# SCH_long_last_clock_v3_2022-12-24.net
KiCad netlist of a schematic drawn in EasyEDA
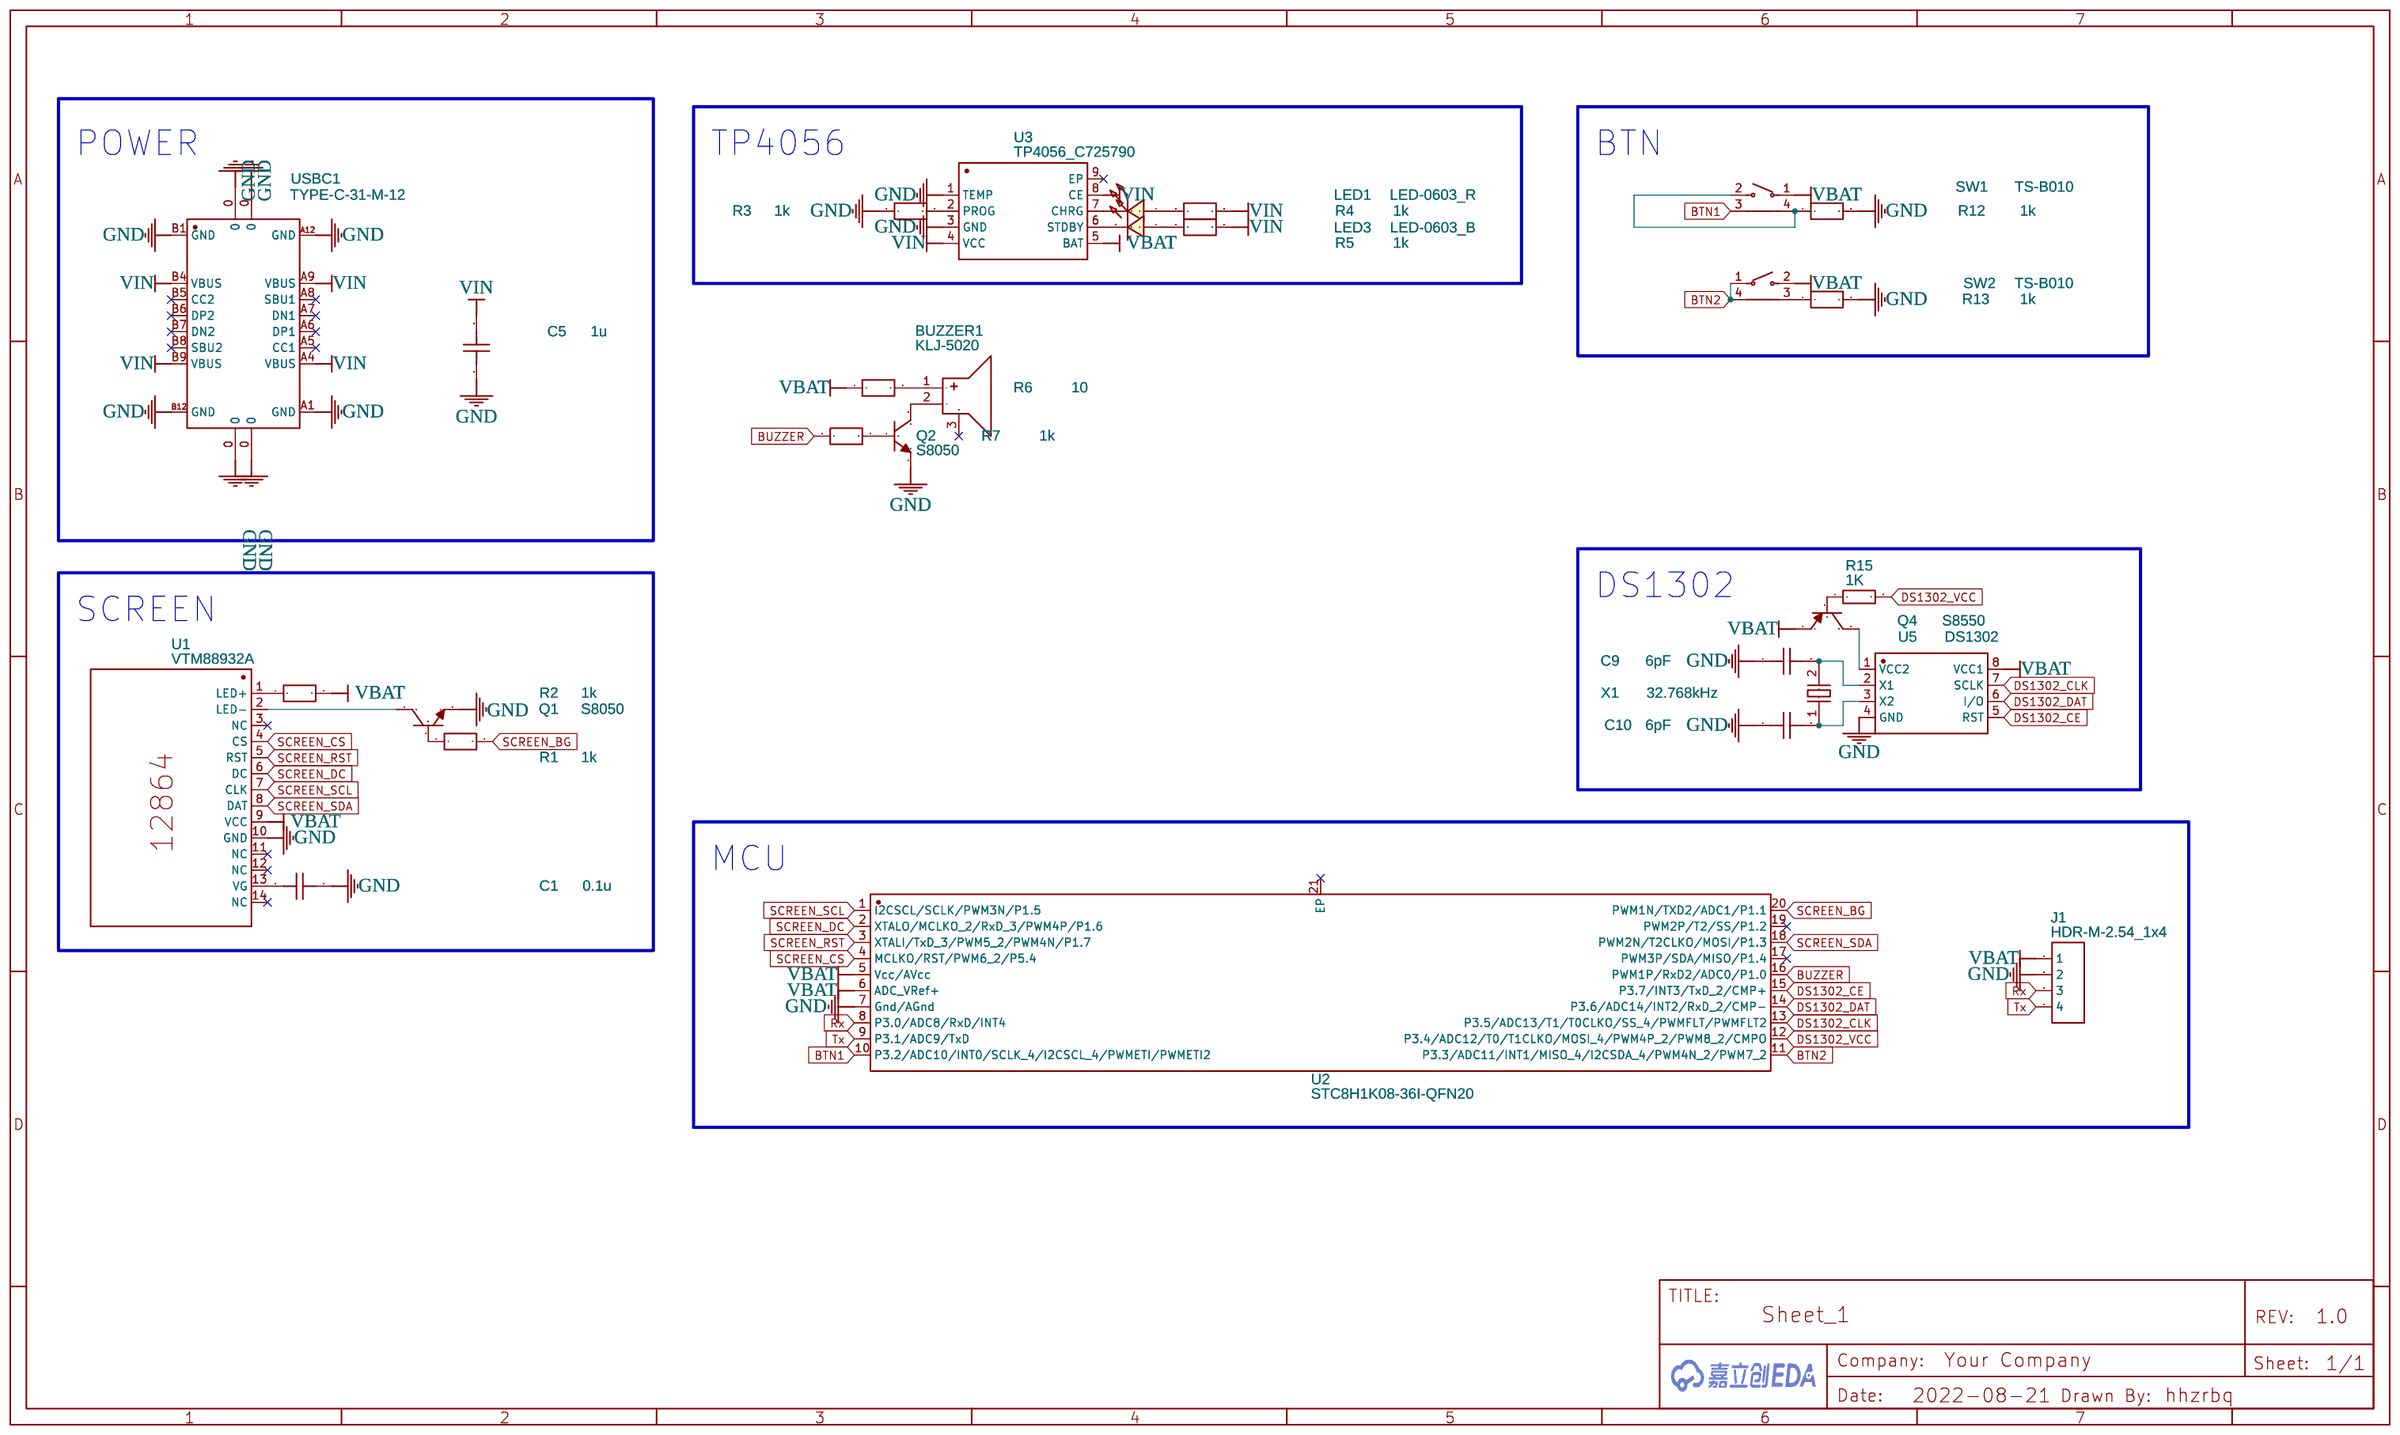
[diagram p0: schematic sheet]

(export (version "E")
  (design (tool "Eeschema 10.0.6"))
  (components
    (comp (ref "BUZZER1")
      (value "KLJ-5020")
      (fields (field (name "BOM_Supplier Part") "C556937"))
      (libsource (lib "") (part "KLJ-5020"))
    )
    (comp (ref "C1") (value "0.1u") (libsource (lib "") (part "C_0603_US")))
    (comp (ref "C5") (value "1u") (libsource (lib "") (part "C_0603_US_1")))
    (comp (ref "C9") (value "6pF") (libsource (lib "") (part "C_0603_US")))
    (comp (ref "C10") (value "6pF") (libsource (lib "") (part "C_0603_US")))
    (comp (ref "J1")
      (value "HDR-M-2.54_1x4")
      (fields (field (name "BOM_Supplier Part") "C124378"))
      (libsource (lib "") (part "HDR-M-2.54_1x4"))
    )
    (comp (ref "LED1")
      (value "LED-0603_R")
      (fields
        (field (name "BOM_Manufacturer Part") "19-217/R6C-AL1M2VY/3T")
        (field (name "BOM_Supplier Part") "C72044")
      )
      (libsource (lib "") (part "LED-0603_R"))
    )
    (comp (ref "LED3")
      (value "LED-0603_B")
      (fields
        (field (name "BOM_Manufacturer Part") "19-217/BHC-ZL1M2RY/3T")
        (field (name "BOM_Supplier Part") "C72041")
      )
      (libsource (lib "") (part "LED-0603_B"))
    )
    (comp (ref "Q1")
      (value "S8050")
      (fields (field (name "BOM_Supplier Part") "C908252"))
      (libsource (lib "") (part "S8050_C908252"))
    )
    (comp (ref "Q2")
      (value "S8050")
      (fields (field (name "BOM_Supplier Part") "C908252"))
      (libsource (lib "") (part "S8050_C908252_1"))
    )
    (comp (ref "Q4")
      (value "S8550")
      (fields (field (name "BOM_Supplier Part") "C2894712"))
      (libsource (lib "") (part "S8550_C2894712"))
    )
    (comp (ref "R1") (value "1k") (libsource (lib "") (part "R_0603_EU")))
    (comp (ref "R2") (value "1k") (libsource (lib "") (part "R_0603_EU")))
    (comp (ref "R3") (value "1k") (libsource (lib "") (part "R_0603_EU")))
    (comp (ref "R4") (value "1k") (libsource (lib "") (part "R_0603_EU")))
    (comp (ref "R5") (value "1k") (libsource (lib "") (part "R_0603_EU")))
    (comp (ref "R6") (value "10") (libsource (lib "") (part "R_0603_EU")))
    (comp (ref "R7") (value "1k") (libsource (lib "") (part "R_0603_EU")))
    (comp (ref "R12") (value "1k") (libsource (lib "") (part "R_0603_EU")))
    (comp (ref "R13") (value "1k") (libsource (lib "") (part "R_0603_EU")))
    (comp (ref "R15")
      (value "1K")
      (fields
        (field (name "BOM_Manufacturer Part") "RK73B2ATTD102J")
        (field (name "BOM_Supplier Part") "C159911")
      )
      (libsource (lib "") (part "RK73B2ATTD102J"))
    )
    (comp (ref "SW1") (value "TS-B010") (libsource (lib "") (part "TD-1100SA-250")))
    (comp (ref "SW2") (value "TS-B010") (libsource (lib "") (part "TD-1100SA-250_1")))
    (comp (ref "U1") (value "VTM88932A") (libsource (lib "") (part "VTM88932A")))
    (comp (ref "U2")
      (value "STC8H1K08-36I-QFN20")
      (fields (field (name "BOM_Supplier Part") "C915674"))
      (libsource (lib "") (part "STC8H1K08-36I-QFN20"))
    )
    (comp (ref "U3")
      (value "TP4056_C725790")
      (fields (field (name "BOM_Manufacturer Part") "TP4056") (field (name "BOM_Supplier Part") "C725790"))
      (libsource (lib "") (part "TP4056_C725790"))
    )
    (comp (ref "U5")
      (value "DS1302")
      (fields
        (field (name "BOM_Manufacturer Part") "DS1302M/TR")
        (field (name "BOM_Supplier Part") "C910881")
      )
      (libsource (lib "") (part "DS1302M/TR_C910881"))
    )
    (comp (ref "USBC1")
      (value "TYPE-C-31-M-12")
      (fields (field (name "BOM_Supplier Part") "C165948"))
      (libsource (lib "") (part "TYPE-C-31-M-12"))
    )
    (comp (ref "X1")
      (value "32.768kHz")
      (fields
        (field (name "BOM_Manufacturer Part") "Q13FC13500005")
        (field (name "BOM_Supplier Part") "C841881")
      )
      (libsource (lib "") (part "Q13FC13500005"))
    )
  )
  (nets
    (net (code "1") (name "BTN1") (class "Default")
      (node (ref "SW1") (pin "3") (pinfunction "3_3") (pintype "unspecified"))
      (node (ref "U2") (pin "10") (pinfunction "P3.2/ADC10/INT0/SCLK_4/I2CSCL_4/PWMETI/PWMETI2_10") (pintype "unspecified"))
    )
    (net (code "2") (name "BTN2") (class "Default")
      (node (ref "SW2") (pin "1") (pinfunction "1_1") (pintype "unspecified"))
      (node (ref "SW2") (pin "4") (pinfunction "4_4") (pintype "unspecified"))
      (node (ref "U2") (pin "11") (pinfunction "P3.3/ADC11/INT1/MISO_4/I2CSDA_4/PWM4N_2/PWM7_2_11") (pintype "unspecified"))
    )
    (net (code "3") (name "BUZZER") (class "Default")
      (node (ref "R7") (pin "1") (pinfunction "1_1") (pintype "unspecified"))
      (node (ref "U2") (pin "16") (pinfunction "PWM1P/RxD2/ADC0/P1.0_16") (pintype "unspecified"))
    )
    (net (code "4") (name "DS1302_CE") (class "Default")
      (node (ref "U2") (pin "15") (pinfunction "P3.7/INT3/TxD_2/CMP+_15") (pintype "unspecified"))
      (node (ref "U5") (pin "5") (pinfunction "RST_5") (pintype "unspecified"))
    )
    (net (code "5") (name "DS1302_CLK") (class "Default")
      (node (ref "U2") (pin "13") (pinfunction "P3.5/ADC13/T1/T0CLKO/SS_4/PWMFLT/PWMFLT2_13") (pintype "unspecified"))
      (node (ref "U5") (pin "7") (pinfunction "SCLK_7") (pintype "unspecified"))
    )
    (net (code "6") (name "DS1302_DAT") (class "Default")
      (node (ref "U2") (pin "14") (pinfunction "P3.6/ADC14/INT2/RxD_2/CMP-_14") (pintype "unspecified"))
      (node (ref "U5") (pin "6") (pinfunction "I/O_6") (pintype "unspecified"))
    )
    (net (code "7") (name "DS1302_VCC") (class "Default")
      (node (ref "R15") (pin "2") (pinfunction "2_2") (pintype "unspecified"))
      (node (ref "U2") (pin "12") (pinfunction "P3.4/ADC12/T0/T1CLKO/MOSI_4/PWM4P_2/PWM8_2/CMPO_12") (pintype "unspecified"))
    )
    (net (code "8") (name "GND") (class "Default")
      (node (ref "C1") (pin "2") (pinfunction "2_2") (pintype "unspecified"))
      (node (ref "C10") (pin "1") (pinfunction "1_1") (pintype "unspecified"))
      (node (ref "C5") (pin "1") (pinfunction "1_1") (pintype "unspecified"))
      (node (ref "C9") (pin "1") (pinfunction "1_1") (pintype "unspecified"))
      (node (ref "J1") (pin "2") (pinfunction "2_2") (pintype "unspecified"))
      (node (ref "Q1") (pin "2") (pinfunction "E_2") (pintype "input"))
      (node (ref "Q2") (pin "2") (pinfunction "E_2") (pintype "input"))
      (node (ref "R12") (pin "2") (pinfunction "2_2") (pintype "unspecified"))
      (node (ref "R13") (pin "2") (pinfunction "2_2") (pintype "unspecified"))
      (node (ref "R3") (pin "1") (pinfunction "1_1") (pintype "unspecified"))
      (node (ref "U1") (pin "10") (pinfunction "GND_10") (pintype "unspecified"))
      (node (ref "U2") (pin "7") (pinfunction "Gnd/AGnd_7") (pintype "unspecified"))
      (node (ref "U3") (pin "1") (pinfunction "TEMP_1") (pintype "unspecified"))
      (node (ref "U3") (pin "3") (pinfunction "GND_3") (pintype "unspecified"))
      (node (ref "U5") (pin "4") (pinfunction "GND_4") (pintype "unspecified"))
      (node (ref "USBC1") (pin "0") (pinfunction "0_0") (pintype "unspecified"))
      (node (ref "USBC1") (pin "A1") (pinfunction "GND_A1") (pintype "unspecified"))
      (node (ref "USBC1") (pin "A12") (pinfunction "GND_A12") (pintype "unspecified"))
      (node (ref "USBC1") (pin "B1") (pinfunction "GND_B1") (pintype "unspecified"))
      (node (ref "USBC1") (pin "B12") (pinfunction "GND_B12") (pintype "unspecified"))
    )
    (net (code "9") (name "Net-(BUZZER1-+)") (class "Default")
      (node (ref "BUZZER1") (pin "1") (pinfunction "+_1") (pintype "unspecified"))
      (node (ref "R6") (pin "2") (pinfunction "2_2") (pintype "unspecified"))
    )
    (net (code "10") (name "Net-(BUZZER1--)") (class "Default")
      (node (ref "BUZZER1") (pin "2") (pinfunction "-_2") (pintype "unspecified"))
      (node (ref "Q2") (pin "3") (pinfunction "C_3") (pintype "input"))
    )
    (net (code "11") (name "Net-(LED1-Pad1)") (class "Default")
      (node (ref "LED1") (pin "1") (pinfunction "1_1") (pintype "unspecified"))
      (node (ref "R4") (pin "1") (pinfunction "1_1") (pintype "unspecified"))
    )
    (net (code "12") (name "Net-(LED3-Pad1)") (class "Default")
      (node (ref "LED3") (pin "1") (pinfunction "1_1") (pintype "unspecified"))
      (node (ref "R5") (pin "1") (pinfunction "1_1") (pintype "unspecified"))
    )
    (net (code "13") (name "Net-(Q1-B)") (class "Default")
      (node (ref "Q1") (pin "1") (pinfunction "B_1") (pintype "input"))
      (node (ref "R1") (pin "1") (pinfunction "1_1") (pintype "unspecified"))
    )
    (net (code "14") (name "Net-(Q1-C)") (class "Default")
      (node (ref "Q1") (pin "3") (pinfunction "C_3") (pintype "input"))
      (node (ref "U1") (pin "2") (pinfunction "LED-_2") (pintype "unspecified"))
    )
    (net (code "15") (name "Net-(Q2-B)") (class "Default")
      (node (ref "Q2") (pin "1") (pinfunction "B_1") (pintype "input"))
      (node (ref "R7") (pin "2") (pinfunction "2_2") (pintype "unspecified"))
    )
    (net (code "16") (name "Net-(Q4-B)") (class "Default")
      (node (ref "Q4") (pin "1") (pinfunction "B_1") (pintype "input"))
      (node (ref "R15") (pin "1") (pinfunction "1_1") (pintype "unspecified"))
    )
    (net (code "17") (name "Net-(Q4-C)") (class "Default")
      (node (ref "Q4") (pin "3") (pinfunction "C_3") (pintype "input"))
      (node (ref "U5") (pin "1") (pinfunction "VCC2_1") (pintype "unspecified"))
    )
    (net (code "18") (name "Net-(R12-Pad1)") (class "Default")
      (node (ref "R12") (pin "1") (pinfunction "1_1") (pintype "unspecified"))
      (node (ref "SW1") (pin "2") (pinfunction "2_2") (pintype "unspecified"))
      (node (ref "SW1") (pin "4") (pinfunction "4_4") (pintype "unspecified"))
    )
    (net (code "19") (name "Net-(R13-Pad1)") (class "Default")
      (node (ref "R13") (pin "1") (pinfunction "1_1") (pintype "unspecified"))
      (node (ref "SW2") (pin "3") (pinfunction "3_3") (pintype "unspecified"))
    )
    (net (code "20") (name "Net-(U1-LED+)") (class "Default")
      (node (ref "R2") (pin "1") (pinfunction "1_1") (pintype "unspecified"))
      (node (ref "U1") (pin "1") (pinfunction "LED+_1") (pintype "unspecified"))
    )
    (net (code "21") (name "Net-(U1-VG)") (class "Default")
      (node (ref "C1") (pin "1") (pinfunction "1_1") (pintype "unspecified"))
      (node (ref "U1") (pin "13") (pinfunction "VG_13") (pintype "unspecified"))
    )
    (net (code "22") (name "Net-(U3-CHRG)") (class "Default")
      (node (ref "LED1") (pin "2") (pinfunction "2_2") (pintype "unspecified"))
      (node (ref "U3") (pin "7") (pinfunction "CHRG_7") (pintype "unspecified"))
    )
    (net (code "23") (name "Net-(U3-PROG)") (class "Default")
      (node (ref "R3") (pin "2") (pinfunction "2_2") (pintype "unspecified"))
      (node (ref "U3") (pin "2") (pinfunction "PROG_2") (pintype "unspecified"))
    )
    (net (code "24") (name "Net-(U3-STDBY)") (class "Default")
      (node (ref "LED3") (pin "2") (pinfunction "2_2") (pintype "unspecified"))
      (node (ref "U3") (pin "6") (pinfunction "STDBY_6") (pintype "unspecified"))
    )
    (net (code "25") (name "Net-(U5-X1)") (class "Default")
      (node (ref "C9") (pin "2") (pinfunction "2_2") (pintype "unspecified"))
      (node (ref "U5") (pin "2") (pinfunction "X1_2") (pintype "unspecified"))
      (node (ref "X1") (pin "2") (pinfunction "GND_2") (pintype "input"))
    )
    (net (code "26") (name "Net-(U5-X2)") (class "Default")
      (node (ref "C10") (pin "2") (pinfunction "2_2") (pintype "unspecified"))
      (node (ref "U5") (pin "3") (pinfunction "X2_3") (pintype "unspecified"))
      (node (ref "X1") (pin "1") (pinfunction "1_1") (pintype "input"))
    )
    (net (code "27") (name "Rx") (class "Default")
      (node (ref "J1") (pin "3") (pinfunction "3_3") (pintype "unspecified"))
      (node (ref "U2") (pin "8") (pinfunction "P3.0/ADC8/RxD/INT4_8") (pintype "unspecified"))
    )
    (net (code "28") (name "SCREEN_BG") (class "Default")
      (node (ref "R1") (pin "2") (pinfunction "2_2") (pintype "unspecified"))
      (node (ref "U2") (pin "20") (pinfunction "PWM1N/TXD2/ADC1/P1.1_20") (pintype "unspecified"))
    )
    (net (code "29") (name "SCREEN_CS") (class "Default")
      (node (ref "U1") (pin "4") (pinfunction "CS_4") (pintype "unspecified"))
      (node (ref "U2") (pin "4") (pinfunction "MCLKO/RST/PWM6_2/P5.4_4") (pintype "unspecified"))
    )
    (net (code "30") (name "SCREEN_DC") (class "Default")
      (node (ref "U1") (pin "6") (pinfunction "DC_6") (pintype "unspecified"))
      (node (ref "U2") (pin "2") (pinfunction "XTALO/MCLKO_2/RxD_3/PWM4P/P1.6_2") (pintype "unspecified"))
    )
    (net (code "31") (name "SCREEN_RST") (class "Default")
      (node (ref "U1") (pin "5") (pinfunction "RST_5") (pintype "unspecified"))
      (node (ref "U2") (pin "3") (pinfunction "XTALI/TxD_3/PWM5_2/PWM4N/P1.7_3") (pintype "unspecified"))
    )
    (net (code "32") (name "SCREEN_SCL") (class "Default")
      (node (ref "U1") (pin "7") (pinfunction "CLK_7") (pintype "unspecified"))
      (node (ref "U2") (pin "1") (pinfunction "I2CSCL/SCLK/PWM3N/P1.5_1") (pintype "unspecified"))
    )
    (net (code "33") (name "SCREEN_SDA") (class "Default")
      (node (ref "U1") (pin "8") (pinfunction "DAT_8") (pintype "unspecified"))
      (node (ref "U2") (pin "18") (pinfunction "PWM2N/T2CLKO/MOSI/P1.3_18") (pintype "unspecified"))
    )
    (net (code "34") (name "Tx") (class "Default")
      (node (ref "J1") (pin "4") (pinfunction "4_4") (pintype "unspecified"))
      (node (ref "U2") (pin "9") (pinfunction "P3.1/ADC9/TxD_9") (pintype "unspecified"))
    )
    (net (code "35") (name "VBAT") (class "Default")
      (node (ref "J1") (pin "1") (pinfunction "1_1") (pintype "unspecified"))
      (node (ref "Q4") (pin "2") (pinfunction "E_2") (pintype "input"))
      (node (ref "R2") (pin "2") (pinfunction "2_2") (pintype "unspecified"))
      (node (ref "R6") (pin "1") (pinfunction "1_1") (pintype "unspecified"))
      (node (ref "SW1") (pin "1") (pinfunction "1_1") (pintype "unspecified"))
      (node (ref "SW2") (pin "2") (pinfunction "2_2") (pintype "unspecified"))
      (node (ref "U1") (pin "9") (pinfunction "VCC_9") (pintype "unspecified"))
      (node (ref "U2") (pin "5") (pinfunction "Vcc/AVcc_5") (pintype "unspecified"))
      (node (ref "U2") (pin "6") (pinfunction "ADC_VRef+_6") (pintype "unspecified"))
      (node (ref "U3") (pin "5") (pinfunction "BAT_5") (pintype "unspecified"))
      (node (ref "U5") (pin "8") (pinfunction "VCC1_8") (pintype "unspecified"))
    )
    (net (code "36") (name "VIN") (class "Default")
      (node (ref "C5") (pin "2") (pinfunction "2_2") (pintype "unspecified"))
      (node (ref "R4") (pin "2") (pinfunction "2_2") (pintype "unspecified"))
      (node (ref "R5") (pin "2") (pinfunction "2_2") (pintype "unspecified"))
      (node (ref "U3") (pin "4") (pinfunction "VCC_4") (pintype "unspecified"))
      (node (ref "U3") (pin "8") (pinfunction "CE_8") (pintype "unspecified"))
      (node (ref "USBC1") (pin "A4") (pinfunction "VBUS_A4") (pintype "unspecified"))
      (node (ref "USBC1") (pin "A9") (pinfunction "VBUS_A9") (pintype "unspecified"))
      (node (ref "USBC1") (pin "B4") (pinfunction "VBUS_B4") (pintype "unspecified"))
      (node (ref "USBC1") (pin "B9") (pinfunction "VBUS_B9") (pintype "unspecified"))
    )
    (net (code "37") (name "unconnected-(BUZZER1-NC-Pad3)") (class "Default")
      (node (ref "BUZZER1") (pin "3") (pinfunction "NC_3") (pintype "unspecified+no_connect"))
    )
    (net (code "38") (name "unconnected-(U1-NC-Pad3)") (class "Default")
      (node (ref "U1") (pin "3") (pinfunction "NC_3") (pintype "unspecified+no_connect"))
    )
    (net (code "39") (name "unconnected-(U1-NC-Pad11)") (class "Default")
      (node (ref "U1") (pin "11") (pinfunction "NC_11") (pintype "unspecified+no_connect"))
    )
    (net (code "40") (name "unconnected-(U1-NC-Pad12)") (class "Default")
      (node (ref "U1") (pin "12") (pinfunction "NC_12") (pintype "unspecified+no_connect"))
    )
    (net (code "41") (name "unconnected-(U1-NC-Pad14)") (class "Default")
      (node (ref "U1") (pin "14") (pinfunction "NC_14") (pintype "unspecified+no_connect"))
    )
    (net (code "42") (name "unconnected-(U2-EP-Pad21)") (class "Default")
      (node (ref "U2") (pin "21") (pinfunction "EP_21") (pintype "unspecified+no_connect"))
    )
    (net (code "43") (name "unconnected-(U2-PWM2P{slash}T2{slash}SS{slash}P1.2-Pad19)") (class "Default")
      (node (ref "U2") (pin "19") (pinfunction "PWM2P/T2/SS/P1.2_19") (pintype "unspecified+no_connect"))
    )
    (net (code "44") (name "unconnected-(U2-PWM3P{slash}SDA{slash}MISO{slash}P1.4-Pad17)") (class "Default")
      (node (ref "U2") (pin "17") (pinfunction "PWM3P/SDA/MISO/P1.4_17") (pintype "unspecified+no_connect"))
    )
    (net (code "45") (name "unconnected-(U3-EP-Pad9)") (class "Default")
      (node (ref "U3") (pin "9") (pinfunction "EP_9") (pintype "unspecified+no_connect"))
    )
    (net (code "46") (name "unconnected-(USBC1-CC1-PadA5)") (class "Default")
      (node (ref "USBC1") (pin "A5") (pinfunction "CC1_A5") (pintype "unspecified+no_connect"))
    )
    (net (code "47") (name "unconnected-(USBC1-CC2-PadB5)") (class "Default")
      (node (ref "USBC1") (pin "B5") (pinfunction "CC2_B5") (pintype "unspecified+no_connect"))
    )
    (net (code "48") (name "unconnected-(USBC1-DN1-PadA7)") (class "Default")
      (node (ref "USBC1") (pin "A7") (pinfunction "DN1_A7") (pintype "unspecified+no_connect"))
    )
    (net (code "49") (name "unconnected-(USBC1-DN2-PadB7)") (class "Default")
      (node (ref "USBC1") (pin "B7") (pinfunction "DN2_B7") (pintype "unspecified+no_connect"))
    )
    (net (code "50") (name "unconnected-(USBC1-DP1-PadA6)") (class "Default")
      (node (ref "USBC1") (pin "A6") (pinfunction "DP1_A6") (pintype "unspecified+no_connect"))
    )
    (net (code "51") (name "unconnected-(USBC1-DP2-PadB6)") (class "Default")
      (node (ref "USBC1") (pin "B6") (pinfunction "DP2_B6") (pintype "unspecified+no_connect"))
    )
    (net (code "52") (name "unconnected-(USBC1-SBU1-PadA8)") (class "Default")
      (node (ref "USBC1") (pin "A8") (pinfunction "SBU1_A8") (pintype "unspecified+no_connect"))
    )
    (net (code "53") (name "unconnected-(USBC1-SBU2-PadB8)") (class "Default")
      (node (ref "USBC1") (pin "B8") (pinfunction "SBU2_B8") (pintype "unspecified+no_connect"))
    )
  )
)
